# Sheet_1_2021-05-11.net
KiCad netlist of a schematic drawn in Altium Designer
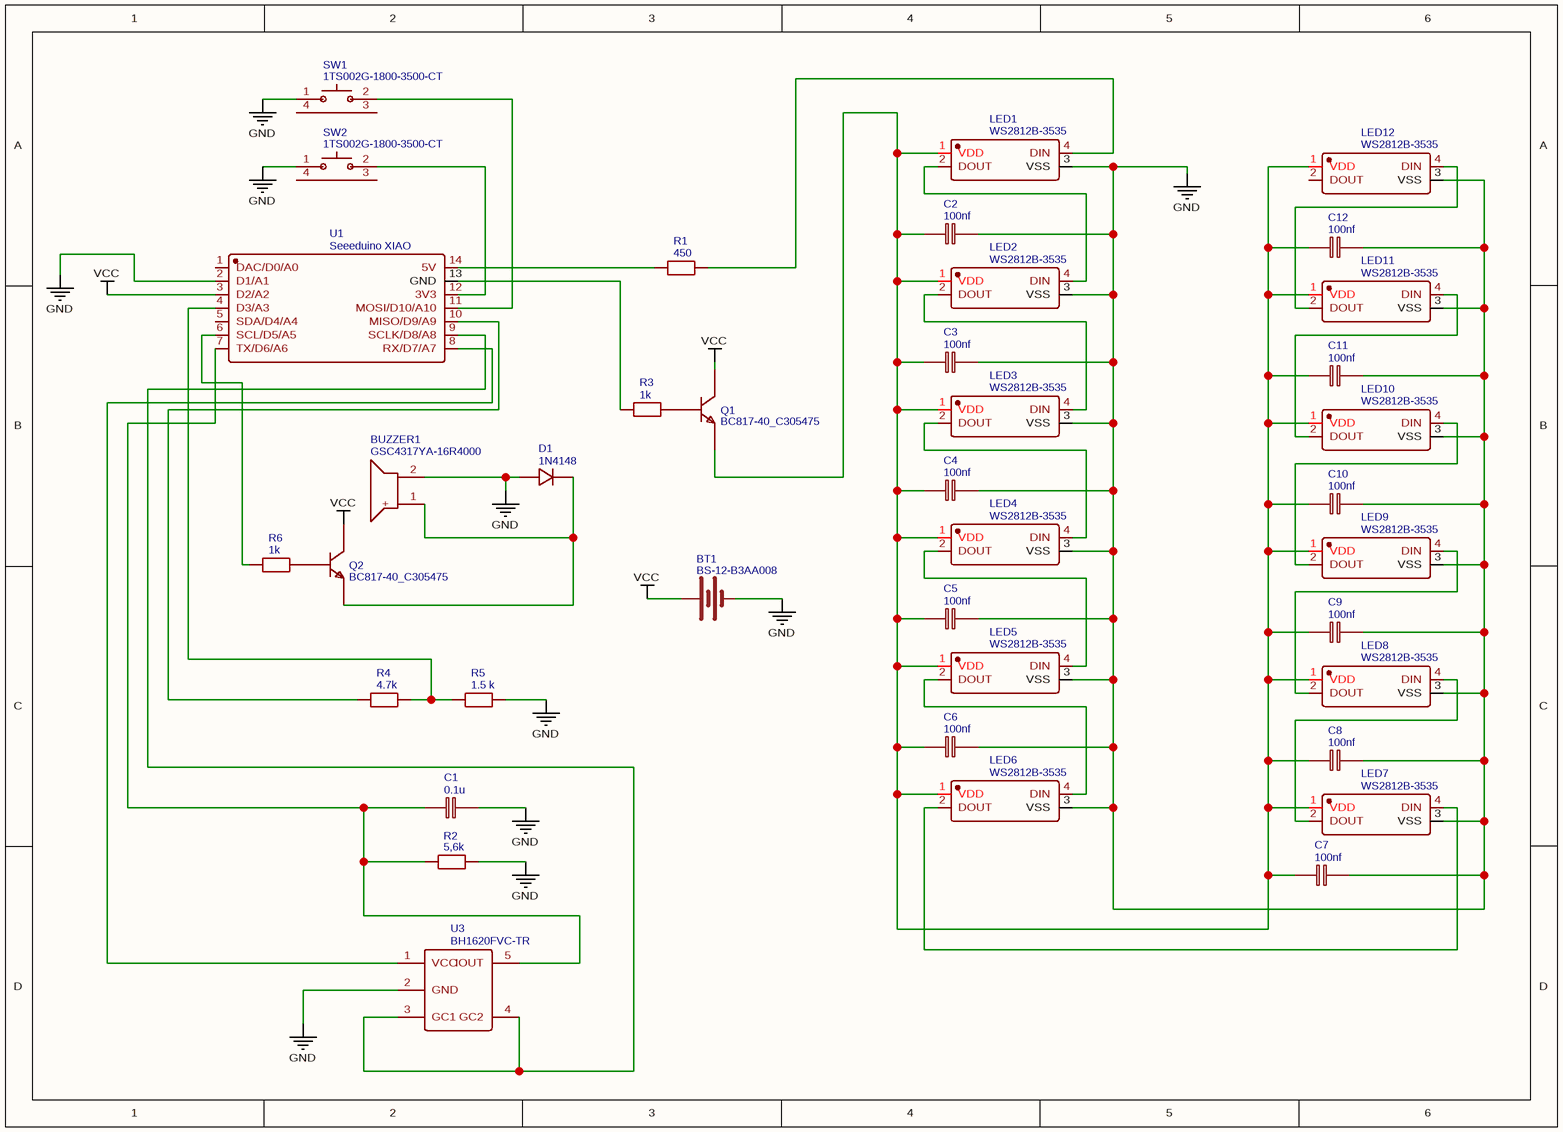
[diagram p0: Sheet_1_2021-05-11.schdoc]

(export (version "E")
  (design (tool "Eeschema 10.0.6"))
  (components
    (comp (ref "BT1")
      (value "BS-12-B3AA008")
      (fields (field (name "BOM_SUPPLIER PART") "C964725") (field (name "CONTRIBUTOR") "LCSC"))
      (libsource (lib "altium-import") (part "root_0_BS-12-B3AA008_"))
    )
    (comp (ref "BUZZER1")
      (value "GSC4317YA-16R4000")
      (fields (field (name "BOM_SUPPLIER PART") "C255307") (field (name "CONTRIBUTOR") "LCSC"))
      (libsource (lib "altium-import") (part "root_0_GSC4317YA-16R4000_"))
    )
    (comp (ref "C1")
      (value "0.1u")
      (fields (field (name "CONTRIBUTOR") "LCEDA_Lib"))
      (libsource (lib "altium-import") (part "root_0_0.1u_"))
    )
    (comp (ref "C2")
      (value "100nf")
      (fields (field (name "CONTRIBUTOR") "LCEDA_Lib"))
      (libsource (lib "altium-import") (part "root_0_100nf_"))
    )
    (comp (ref "C3")
      (value "100nf")
      (fields (field (name "CONTRIBUTOR") "LCEDA_Lib"))
      (libsource (lib "altium-import") (part "root_0_100nf_"))
    )
    (comp (ref "C4")
      (value "100nf")
      (fields (field (name "CONTRIBUTOR") "LCEDA_Lib"))
      (libsource (lib "altium-import") (part "root_0_100nf_"))
    )
    (comp (ref "C5")
      (value "100nf")
      (fields (field (name "CONTRIBUTOR") "LCEDA_Lib"))
      (libsource (lib "altium-import") (part "root_0_100nf_"))
    )
    (comp (ref "C6")
      (value "100nf")
      (fields (field (name "CONTRIBUTOR") "LCEDA_Lib"))
      (libsource (lib "altium-import") (part "root_0_100nf_"))
    )
    (comp (ref "C7")
      (value "100nf")
      (fields (field (name "CONTRIBUTOR") "LCEDA_Lib"))
      (libsource (lib "altium-import") (part "root_0_100nf_"))
    )
    (comp (ref "C8")
      (value "100nf")
      (fields (field (name "CONTRIBUTOR") "LCEDA_Lib"))
      (libsource (lib "altium-import") (part "root_0_100nf_"))
    )
    (comp (ref "C9")
      (value "100nf")
      (fields (field (name "CONTRIBUTOR") "LCEDA_Lib"))
      (libsource (lib "altium-import") (part "root_0_100nf_"))
    )
    (comp (ref "C10")
      (value "100nf")
      (fields (field (name "CONTRIBUTOR") "LCEDA_Lib"))
      (libsource (lib "altium-import") (part "root_0_100nf_"))
    )
    (comp (ref "C11")
      (value "100nf")
      (fields (field (name "CONTRIBUTOR") "LCEDA_Lib"))
      (libsource (lib "altium-import") (part "root_0_100nf_"))
    )
    (comp (ref "C12")
      (value "100nf")
      (fields (field (name "CONTRIBUTOR") "LCEDA_Lib"))
      (libsource (lib "altium-import") (part "root_0_100nf_"))
    )
    (comp (ref "D1")
      (value "1N4148")
      (fields (field (name "BOM_SUPPLIER PART") "C14516") (field (name "CONTRIBUTOR") "LCEDA_Lib"))
      (libsource (lib "altium-import") (part "root_0_1N4148_"))
    )
    (comp (ref "LED1")
      (value "WS2812B-3535")
      (fields (field (name "BOM_SUPPLIER PART") "C114583") (field (name "CONTRIBUTOR") "LCSC"))
      (libsource (lib "altium-import") (part "root_0_WS2812B-3535_"))
    )
    (comp (ref "LED2")
      (value "WS2812B-3535")
      (fields (field (name "BOM_SUPPLIER PART") "C114583") (field (name "CONTRIBUTOR") "LCSC"))
      (libsource (lib "altium-import") (part "root_0_WS2812B-3535_"))
    )
    (comp (ref "LED3")
      (value "WS2812B-3535")
      (fields (field (name "BOM_SUPPLIER PART") "C114583") (field (name "CONTRIBUTOR") "LCSC"))
      (libsource (lib "altium-import") (part "root_0_WS2812B-3535_"))
    )
    (comp (ref "LED4")
      (value "WS2812B-3535")
      (fields (field (name "BOM_SUPPLIER PART") "C114583") (field (name "CONTRIBUTOR") "LCSC"))
      (libsource (lib "altium-import") (part "root_0_WS2812B-3535_"))
    )
    (comp (ref "LED5")
      (value "WS2812B-3535")
      (fields (field (name "BOM_SUPPLIER PART") "C114583") (field (name "CONTRIBUTOR") "LCSC"))
      (libsource (lib "altium-import") (part "root_0_WS2812B-3535_"))
    )
    (comp (ref "LED6")
      (value "WS2812B-3535")
      (fields (field (name "BOM_SUPPLIER PART") "C114583") (field (name "CONTRIBUTOR") "LCSC"))
      (libsource (lib "altium-import") (part "root_0_WS2812B-3535_"))
    )
    (comp (ref "LED7")
      (value "WS2812B-3535")
      (fields (field (name "BOM_SUPPLIER PART") "C114583") (field (name "CONTRIBUTOR") "LCSC"))
      (libsource (lib "altium-import") (part "root_0_WS2812B-3535_"))
    )
    (comp (ref "LED8")
      (value "WS2812B-3535")
      (fields (field (name "BOM_SUPPLIER PART") "C114583") (field (name "CONTRIBUTOR") "LCSC"))
      (libsource (lib "altium-import") (part "root_0_WS2812B-3535_"))
    )
    (comp (ref "LED9")
      (value "WS2812B-3535")
      (fields (field (name "BOM_SUPPLIER PART") "C114583") (field (name "CONTRIBUTOR") "LCSC"))
      (libsource (lib "altium-import") (part "root_0_WS2812B-3535_"))
    )
    (comp (ref "LED10")
      (value "WS2812B-3535")
      (fields (field (name "BOM_SUPPLIER PART") "C114583") (field (name "CONTRIBUTOR") "LCSC"))
      (libsource (lib "altium-import") (part "root_0_WS2812B-3535_"))
    )
    (comp (ref "LED11")
      (value "WS2812B-3535")
      (fields (field (name "BOM_SUPPLIER PART") "C114583") (field (name "CONTRIBUTOR") "LCSC"))
      (libsource (lib "altium-import") (part "root_0_WS2812B-3535_"))
    )
    (comp (ref "LED12")
      (value "WS2812B-3535")
      (fields (field (name "BOM_SUPPLIER PART") "C114583") (field (name "CONTRIBUTOR") "LCSC"))
      (libsource (lib "altium-import") (part "root_0_WS2812B-3535_"))
    )
    (comp (ref "Q1")
      (value "BC817-40_C305475")
      (fields
        (field (name "BOM_SUPPLIER PART") "C305475")
        (field (name "BOM_MANUFACTURER PART") "BC817-40")
        (field (name "CONTRIBUTOR") "LCSC")
      )
      (libsource (lib "altium-import") (part "root_0_BC817-40_C305475_"))
    )
    (comp (ref "Q2")
      (value "BC817-40_C305475")
      (fields
        (field (name "BOM_SUPPLIER PART") "C305475")
        (field (name "BOM_MANUFACTURER PART") "BC817-40")
        (field (name "CONTRIBUTOR") "LCSC")
      )
      (libsource (lib "altium-import") (part "root_0_BC817-40_C305475_"))
    )
    (comp (ref "R1")
      (value "450")
      (fields (field (name "CONTRIBUTOR") "LCEDA_Lib"))
      (libsource (lib "altium-import") (part "root_0_450_"))
    )
    (comp (ref "R2")
      (value "5,6k")
      (fields (field (name "CONTRIBUTOR") "LCEDA_Lib"))
      (libsource (lib "altium-import") (part "root_0_5,6k_"))
    )
    (comp (ref "R3")
      (value "1k")
      (fields (field (name "CONTRIBUTOR") "LCEDA_Lib"))
      (libsource (lib "altium-import") (part "root_0_1k_"))
    )
    (comp (ref "R4")
      (value "4.7k")
      (fields (field (name "CONTRIBUTOR") "LCEDA_Lib"))
      (libsource (lib "altium-import") (part "root_0_4.7k_"))
    )
    (comp (ref "R5")
      (value "1.5 k")
      (fields (field (name "CONTRIBUTOR") "LCEDA_Lib"))
      (libsource (lib "altium-import") (part "root_0_1.5 k_"))
    )
    (comp (ref "R6")
      (value "1k")
      (fields (field (name "CONTRIBUTOR") "LCEDA_Lib"))
      (libsource (lib "altium-import") (part "root_0_1k_"))
    )
    (comp (ref "SW1")
      (value "1TS002G-1800-3500-CT")
      (fields (field (name "BOM_SUPPLIER PART") "C319375") (field (name "CONTRIBUTOR") "LCSC"))
      (libsource (lib "altium-import") (part "root_0_1TS002G-1800-3500-CT_"))
    )
    (comp (ref "SW2")
      (value "1TS002G-1800-3500-CT")
      (fields (field (name "BOM_SUPPLIER PART") "C319375") (field (name "CONTRIBUTOR") "LCSC"))
      (libsource (lib "altium-import") (part "root_0_1TS002G-1800-3500-CT_"))
    )
    (comp (ref "U1")
      (value "Seeeduino XIAO")
      (fields (field (name "CONTRIBUTOR") "paul_1809"))
      (libsource (lib "altium-import") (part "root_0_Seeeduino XIAO_"))
    )
    (comp (ref "U3")
      (value "BH1620FVC-TR")
      (fields (field (name "BOM_SUPPLIER PART") "C84991"))
      (libsource (lib "altium-import") (part "root_0_BH1620FVC-TR_"))
    )
  )
  (nets
    (net (code "1") (name "GND") (class "Default")
      (node (ref "BT1") (pin "2") (pinfunction "-_2") (pintype "passive"))
      (node (ref "BUZZER1") (pin "2") (pinfunction "2_2") (pintype "passive"))
      (node (ref "C1") (pin "2") (pinfunction "2_2") (pintype "passive"))
      (node (ref "C10") (pin "2") (pinfunction "2_2") (pintype "passive"))
      (node (ref "C11") (pin "2") (pinfunction "2_2") (pintype "passive"))
      (node (ref "C12") (pin "2") (pinfunction "2_2") (pintype "passive"))
      (node (ref "C2") (pin "2") (pinfunction "2_2") (pintype "passive"))
      (node (ref "C3") (pin "2") (pinfunction "2_2") (pintype "passive"))
      (node (ref "C4") (pin "2") (pinfunction "2_2") (pintype "passive"))
      (node (ref "C5") (pin "2") (pinfunction "2_2") (pintype "passive"))
      (node (ref "C6") (pin "2") (pinfunction "2_2") (pintype "passive"))
      (node (ref "C7") (pin "2") (pinfunction "2_2") (pintype "passive"))
      (node (ref "C8") (pin "2") (pinfunction "2_2") (pintype "passive"))
      (node (ref "C9") (pin "2") (pinfunction "2_2") (pintype "passive"))
      (node (ref "D1") (pin "1") (pinfunction "1_1") (pintype "passive"))
      (node (ref "LED1") (pin "3") (pinfunction "VSS_3") (pintype "passive"))
      (node (ref "LED10") (pin "3") (pinfunction "VSS_3") (pintype "passive"))
      (node (ref "LED11") (pin "3") (pinfunction "VSS_3") (pintype "passive"))
      (node (ref "LED12") (pin "3") (pinfunction "VSS_3") (pintype "passive"))
      (node (ref "LED2") (pin "3") (pinfunction "VSS_3") (pintype "passive"))
      (node (ref "LED3") (pin "3") (pinfunction "VSS_3") (pintype "passive"))
      (node (ref "LED4") (pin "3") (pinfunction "VSS_3") (pintype "passive"))
      (node (ref "LED5") (pin "3") (pinfunction "VSS_3") (pintype "passive"))
      (node (ref "LED6") (pin "3") (pinfunction "VSS_3") (pintype "passive"))
      (node (ref "LED7") (pin "3") (pinfunction "VSS_3") (pintype "passive"))
      (node (ref "LED8") (pin "3") (pinfunction "VSS_3") (pintype "passive"))
      (node (ref "LED9") (pin "3") (pinfunction "VSS_3") (pintype "passive"))
      (node (ref "R2") (pin "2") (pinfunction "2_2") (pintype "passive"))
      (node (ref "R5") (pin "2") (pinfunction "2_2") (pintype "passive"))
      (node (ref "SW1") (pin "1") (pinfunction "A_1") (pintype "passive"))
      (node (ref "SW2") (pin "1") (pinfunction "A_1") (pintype "passive"))
      (node (ref "U1") (pin "2") (pinfunction "D1/A1_2") (pintype "passive"))
      (node (ref "U3") (pin "2") (pinfunction "GND_2") (pintype "passive"))
    )
    (net (code "2") (name "Net-(BUZZER1-+)") (class "Default")
      (node (ref "BUZZER1") (pin "1") (pinfunction "+_1") (pintype "passive"))
      (node (ref "D1") (pin "2") (pinfunction "2_2") (pintype "passive"))
      (node (ref "Q2") (pin "2") (pinfunction "E_2") (pintype "passive"))
    )
    (net (code "3") (name "Net-(LED1-DIN)") (class "Default")
      (node (ref "LED1") (pin "4") (pinfunction "DIN_4") (pintype "passive"))
      (node (ref "R1") (pin "2") (pinfunction "2_2") (pintype "passive"))
    )
    (net (code "4") (name "Net-(LED1-DOUT)") (class "Default")
      (node (ref "LED1") (pin "2") (pinfunction "DOUT_2") (pintype "passive"))
      (node (ref "LED2") (pin "4") (pinfunction "DIN_4") (pintype "passive"))
    )
    (net (code "5") (name "Net-(LED1-VDD)") (class "Default")
      (node (ref "C10") (pin "1") (pinfunction "1_1") (pintype "passive"))
      (node (ref "C11") (pin "1") (pinfunction "1_1") (pintype "passive"))
      (node (ref "C12") (pin "1") (pinfunction "1_1") (pintype "passive"))
      (node (ref "C2") (pin "1") (pinfunction "1_1") (pintype "passive"))
      (node (ref "C3") (pin "1") (pinfunction "1_1") (pintype "passive"))
      (node (ref "C4") (pin "1") (pinfunction "1_1") (pintype "passive"))
      (node (ref "C5") (pin "1") (pinfunction "1_1") (pintype "passive"))
      (node (ref "C6") (pin "1") (pinfunction "1_1") (pintype "passive"))
      (node (ref "C7") (pin "1") (pinfunction "1_1") (pintype "passive"))
      (node (ref "C8") (pin "1") (pinfunction "1_1") (pintype "passive"))
      (node (ref "C9") (pin "1") (pinfunction "1_1") (pintype "passive"))
      (node (ref "LED1") (pin "1") (pinfunction "VDD_1") (pintype "passive"))
      (node (ref "LED10") (pin "1") (pinfunction "VDD_1") (pintype "passive"))
      (node (ref "LED11") (pin "1") (pinfunction "VDD_1") (pintype "passive"))
      (node (ref "LED12") (pin "1") (pinfunction "VDD_1") (pintype "passive"))
      (node (ref "LED2") (pin "1") (pinfunction "VDD_1") (pintype "passive"))
      (node (ref "LED3") (pin "1") (pinfunction "VDD_1") (pintype "passive"))
      (node (ref "LED4") (pin "1") (pinfunction "VDD_1") (pintype "passive"))
      (node (ref "LED5") (pin "1") (pinfunction "VDD_1") (pintype "passive"))
      (node (ref "LED6") (pin "1") (pinfunction "VDD_1") (pintype "passive"))
      (node (ref "LED7") (pin "1") (pinfunction "VDD_1") (pintype "passive"))
      (node (ref "LED8") (pin "1") (pinfunction "VDD_1") (pintype "passive"))
      (node (ref "LED9") (pin "1") (pinfunction "VDD_1") (pintype "passive"))
      (node (ref "Q1") (pin "2") (pinfunction "E_2") (pintype "passive"))
    )
    (net (code "6") (name "Net-(LED2-DOUT)") (class "Default")
      (node (ref "LED2") (pin "2") (pinfunction "DOUT_2") (pintype "passive"))
      (node (ref "LED3") (pin "4") (pinfunction "DIN_4") (pintype "passive"))
    )
    (net (code "7") (name "Net-(LED3-DOUT)") (class "Default")
      (node (ref "LED3") (pin "2") (pinfunction "DOUT_2") (pintype "passive"))
      (node (ref "LED4") (pin "4") (pinfunction "DIN_4") (pintype "passive"))
    )
    (net (code "8") (name "Net-(LED4-DOUT)") (class "Default")
      (node (ref "LED4") (pin "2") (pinfunction "DOUT_2") (pintype "passive"))
      (node (ref "LED5") (pin "4") (pinfunction "DIN_4") (pintype "passive"))
    )
    (net (code "9") (name "Net-(LED5-DOUT)") (class "Default")
      (node (ref "LED5") (pin "2") (pinfunction "DOUT_2") (pintype "passive"))
      (node (ref "LED6") (pin "4") (pinfunction "DIN_4") (pintype "passive"))
    )
    (net (code "10") (name "Net-(LED6-DOUT)") (class "Default")
      (node (ref "LED6") (pin "2") (pinfunction "DOUT_2") (pintype "passive"))
      (node (ref "LED7") (pin "4") (pinfunction "DIN_4") (pintype "passive"))
    )
    (net (code "11") (name "Net-(LED7-DOUT)") (class "Default")
      (node (ref "LED7") (pin "2") (pinfunction "DOUT_2") (pintype "passive"))
      (node (ref "LED8") (pin "4") (pinfunction "DIN_4") (pintype "passive"))
    )
    (net (code "12") (name "Net-(LED8-DOUT)") (class "Default")
      (node (ref "LED8") (pin "2") (pinfunction "DOUT_2") (pintype "passive"))
      (node (ref "LED9") (pin "4") (pinfunction "DIN_4") (pintype "passive"))
    )
    (net (code "13") (name "Net-(LED10-DIN)") (class "Default")
      (node (ref "LED10") (pin "4") (pinfunction "DIN_4") (pintype "passive"))
      (node (ref "LED9") (pin "2") (pinfunction "DOUT_2") (pintype "passive"))
    )
    (net (code "14") (name "Net-(LED10-DOUT)") (class "Default")
      (node (ref "LED10") (pin "2") (pinfunction "DOUT_2") (pintype "passive"))
      (node (ref "LED11") (pin "4") (pinfunction "DIN_4") (pintype "passive"))
    )
    (net (code "15") (name "Net-(LED11-DOUT)") (class "Default")
      (node (ref "LED11") (pin "2") (pinfunction "DOUT_2") (pintype "passive"))
      (node (ref "LED12") (pin "4") (pinfunction "DIN_4") (pintype "passive"))
    )
    (net (code "16") (name "Net-(Q1-B)") (class "Default")
      (node (ref "Q1") (pin "1") (pinfunction "B_1") (pintype "passive"))
      (node (ref "R3") (pin "2") (pinfunction "2_2") (pintype "passive"))
    )
    (net (code "17") (name "Net-(Q2-B)") (class "Default")
      (node (ref "Q2") (pin "1") (pinfunction "B_1") (pintype "passive"))
      (node (ref "R6") (pin "2") (pinfunction "2_2") (pintype "passive"))
    )
    (net (code "18") (name "Net-(SW1-B)") (class "Default")
      (node (ref "SW1") (pin "2") (pinfunction "B_2") (pintype "passive"))
      (node (ref "U1") (pin "11") (pinfunction "MOSI/D10/A10_11") (pintype "passive"))
    )
    (net (code "19") (name "Net-(SW2-B)") (class "Default")
      (node (ref "SW2") (pin "2") (pinfunction "B_2") (pintype "passive"))
      (node (ref "U1") (pin "12") (pinfunction "3V3_12") (pintype "passive"))
    )
    (net (code "20") (name "Net-(U1-5V)") (class "Default")
      (node (ref "R1") (pin "1") (pinfunction "1_1") (pintype "passive"))
      (node (ref "U1") (pin "14") (pinfunction "5V_14") (pintype "passive"))
    )
    (net (code "21") (name "Net-(U1-D3{slash}A3)") (class "Default")
      (node (ref "R4") (pin "2") (pinfunction "2_2") (pintype "passive"))
      (node (ref "R5") (pin "1") (pinfunction "1_1") (pintype "passive"))
      (node (ref "U1") (pin "4") (pinfunction "D3/A3_4") (pintype "passive"))
    )
    (net (code "22") (name "Net-(U1-GND)") (class "Default")
      (node (ref "R3") (pin "1") (pinfunction "1_1") (pintype "passive"))
      (node (ref "U1") (pin "13") (pinfunction "GND_13") (pintype "passive"))
    )
    (net (code "23") (name "Net-(U1-MISO{slash}D9{slash}A9)") (class "Default")
      (node (ref "R4") (pin "1") (pinfunction "1_1") (pintype "passive"))
      (node (ref "U1") (pin "10") (pinfunction "MISO/D9/A9_10") (pintype "passive"))
    )
    (net (code "24") (name "Net-(U1-RX{slash}D7{slash}A7)") (class "Default")
      (node (ref "U1") (pin "8") (pinfunction "RX/D7/A7_8") (pintype "passive"))
      (node (ref "U3") (pin "1") (pinfunction "VCC_1") (pintype "passive"))
    )
    (net (code "25") (name "Net-(U1-SCLK{slash}D8{slash}A8)") (class "Default")
      (node (ref "U1") (pin "9") (pinfunction "SCLK/D8/A8_9") (pintype "passive"))
      (node (ref "U3") (pin "3") (pinfunction "GC1_3") (pintype "passive"))
      (node (ref "U3") (pin "4") (pinfunction "GC2_4") (pintype "passive"))
    )
    (net (code "26") (name "Net-(U1-SCL{slash}D5{slash}A5)") (class "Default")
      (node (ref "R6") (pin "1") (pinfunction "1_1") (pintype "passive"))
      (node (ref "U1") (pin "6") (pinfunction "SCL/D5/A5_6") (pintype "passive"))
    )
    (net (code "27") (name "Net-(U1-TX{slash}D6{slash}A6)") (class "Default")
      (node (ref "C1") (pin "1") (pinfunction "1_1") (pintype "passive"))
      (node (ref "R2") (pin "1") (pinfunction "1_1") (pintype "passive"))
      (node (ref "U1") (pin "7") (pinfunction "TX/D6/A6_7") (pintype "passive"))
      (node (ref "U3") (pin "5") (pinfunction "IOUT_5") (pintype "passive"))
    )
    (net (code "28") (name "VCC") (class "Default")
      (node (ref "BT1") (pin "1") (pinfunction "+_1") (pintype "passive"))
      (node (ref "Q1") (pin "3") (pinfunction "C_3") (pintype "passive"))
      (node (ref "Q2") (pin "3") (pinfunction "C_3") (pintype "passive"))
      (node (ref "U1") (pin "3") (pinfunction "D2/A2_3") (pintype "passive"))
    )
    (net (code "29") (name "unconnected-(LED12-DOUT-Pad2)") (class "Default")
      (node (ref "LED12") (pin "2") (pinfunction "DOUT_2") (pintype "passive"))
    )
    (net (code "30") (name "unconnected-(SW1-Pad3)") (class "Default")
      (node (ref "SW1") (pin "3") (pinfunction "3_3") (pintype "passive"))
    )
    (net (code "31") (name "unconnected-(SW1-Pad4)") (class "Default")
      (node (ref "SW1") (pin "4") (pinfunction "4_4") (pintype "passive"))
    )
    (net (code "32") (name "unconnected-(SW2-Pad3)") (class "Default")
      (node (ref "SW2") (pin "3") (pinfunction "3_3") (pintype "passive"))
    )
    (net (code "33") (name "unconnected-(SW2-Pad4)") (class "Default")
      (node (ref "SW2") (pin "4") (pinfunction "4_4") (pintype "passive"))
    )
    (net (code "34") (name "unconnected-(U1-DAC{slash}D0{slash}A0-Pad1)") (class "Default")
      (node (ref "U1") (pin "1") (pinfunction "DAC/D0/A0_1") (pintype "passive"))
    )
    (net (code "35") (name "unconnected-(U1-SDA{slash}D4{slash}A4-Pad5)") (class "Default")
      (node (ref "U1") (pin "5") (pinfunction "SDA/D4/A4_5") (pintype "passive"))
    )
  )
)
